# ZXS_I2_kartridz.net
KiCad netlist of a schematic drawn in EAGLE
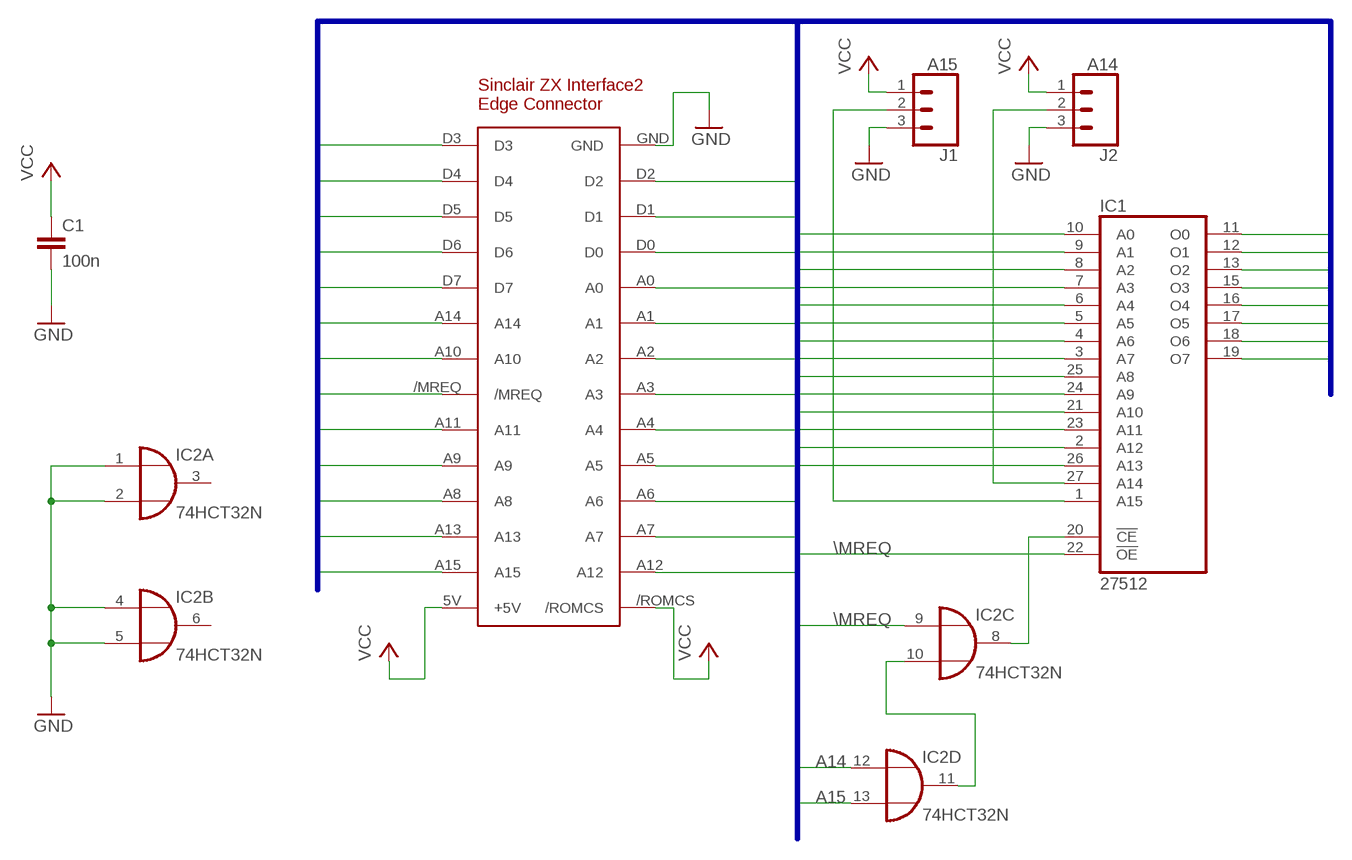
[diagram p0: schematic, sheet 1]

(export (version "E")
  (design (tool "Eeschema 10.0.6"))
  (components
    (comp (ref "C1")
      (value "100n")
      (footprint "eagle-import:C050-024X044")
      (libsource (lib "eagle-import") (part "C-EU050-024X044"))
    )
    (comp (ref "IC1")
      (value "27512")
      (footprint "eagle-import:DIL28")
      (libsource (lib "eagle-import") (part "27512"))
    )
    (comp (ref "IC2")
      (value "74HCT32N")
      (footprint "eagle-import:DIL14")
      (libsource (lib "eagle-import") (part "7432NHCT"))
    )
    (comp (ref "J1")
      (value "A15")
      (footprint "eagle-import:1X03")
      (libsource (lib "eagle-import") (part "CONN_03"))
    )
    (comp (ref "J2")
      (value "A14")
      (footprint "eagle-import:1X03")
      (libsource (lib "eagle-import") (part "CONN_03"))
    )
    (comp (ref "U$1")
      (value "ZX_I2_ROM_EDGE_CONNECTOR")
      (footprint "eagle-import:ZX_I2_ROM_EDGE_CONNECTOR_V2")
      (libsource (lib "eagle-import") (part "ZX_I2_ROM_EDGE_CONNECTOR"))
    )
  )
  (nets
    (net (code "1") (name "/A0") (class "Default")
      (node (ref "IC1") (pin "10") (pinfunction "A0_10") (pintype "input"))
      (node (ref "U$1") (pin "A0") (pinfunction "A0_A0") (pintype "bidirectional"))
    )
    (net (code "2") (name "/A1") (class "Default")
      (node (ref "IC1") (pin "9") (pinfunction "A1_9") (pintype "input"))
      (node (ref "U$1") (pin "A1") (pinfunction "A1_A1") (pintype "bidirectional"))
    )
    (net (code "3") (name "/A2") (class "Default")
      (node (ref "IC1") (pin "8") (pinfunction "A2_8") (pintype "input"))
      (node (ref "U$1") (pin "A2") (pinfunction "A2_A2") (pintype "bidirectional"))
    )
    (net (code "4") (name "/A3") (class "Default")
      (node (ref "IC1") (pin "7") (pinfunction "A3_7") (pintype "input"))
      (node (ref "U$1") (pin "A3") (pinfunction "A3_A3") (pintype "bidirectional"))
    )
    (net (code "5") (name "/A4") (class "Default")
      (node (ref "IC1") (pin "6") (pinfunction "A4_6") (pintype "input"))
      (node (ref "U$1") (pin "A4") (pinfunction "A4_A4") (pintype "bidirectional"))
    )
    (net (code "6") (name "/A5") (class "Default")
      (node (ref "IC1") (pin "5") (pinfunction "A5_5") (pintype "input"))
      (node (ref "U$1") (pin "A5") (pinfunction "A5_A5") (pintype "bidirectional"))
    )
    (net (code "7") (name "/A6") (class "Default")
      (node (ref "IC1") (pin "4") (pinfunction "A6_4") (pintype "input"))
      (node (ref "U$1") (pin "A6") (pinfunction "A6_A6") (pintype "bidirectional"))
    )
    (net (code "8") (name "/A7") (class "Default")
      (node (ref "IC1") (pin "3") (pinfunction "A7_3") (pintype "input"))
      (node (ref "U$1") (pin "A7") (pinfunction "A7_A7") (pintype "bidirectional"))
    )
    (net (code "9") (name "/A8") (class "Default")
      (node (ref "IC1") (pin "25") (pinfunction "A8_25") (pintype "input"))
      (node (ref "U$1") (pin "A8") (pinfunction "A8_A8") (pintype "bidirectional"))
    )
    (net (code "10") (name "/A9") (class "Default")
      (node (ref "IC1") (pin "24") (pinfunction "A9_24") (pintype "input"))
      (node (ref "U$1") (pin "A9") (pinfunction "A9_A9") (pintype "bidirectional"))
    )
    (net (code "11") (name "/A10") (class "Default")
      (node (ref "IC1") (pin "21") (pinfunction "A10_21") (pintype "input"))
      (node (ref "U$1") (pin "A10") (pinfunction "A10_A10") (pintype "bidirectional"))
    )
    (net (code "12") (name "/A11") (class "Default")
      (node (ref "IC1") (pin "23") (pinfunction "A11_23") (pintype "input"))
      (node (ref "U$1") (pin "A11") (pinfunction "A11_A11") (pintype "bidirectional"))
    )
    (net (code "13") (name "/A12") (class "Default")
      (node (ref "IC1") (pin "2") (pinfunction "A12_2") (pintype "input"))
      (node (ref "U$1") (pin "A12") (pinfunction "A12_A12") (pintype "bidirectional"))
    )
    (net (code "14") (name "/A13") (class "Default")
      (node (ref "IC1") (pin "26") (pinfunction "A13_26") (pintype "input"))
      (node (ref "U$1") (pin "A13") (pinfunction "A13_A13") (pintype "bidirectional"))
    )
    (net (code "15") (name "/A14") (class "Default")
      (node (ref "IC2") (pin "12") (pinfunction "I0_12") (pintype "input"))
      (node (ref "U$1") (pin "A14") (pinfunction "A14_A14") (pintype "bidirectional"))
    )
    (net (code "16") (name "/A15") (class "Default")
      (node (ref "IC2") (pin "13") (pinfunction "I1_13") (pintype "input"))
      (node (ref "U$1") (pin "A15") (pinfunction "A15_A15") (pintype "bidirectional"))
    )
    (net (code "17") (name "/D0") (class "Default")
      (node (ref "IC1") (pin "11") (pinfunction "O0_11") (pintype "tri_state"))
      (node (ref "U$1") (pin "D0") (pinfunction "D0_D0") (pintype "bidirectional"))
    )
    (net (code "18") (name "/D1") (class "Default")
      (node (ref "IC1") (pin "12") (pinfunction "O1_12") (pintype "tri_state"))
      (node (ref "U$1") (pin "D1") (pinfunction "D1_D1") (pintype "bidirectional"))
    )
    (net (code "19") (name "/D2") (class "Default")
      (node (ref "IC1") (pin "13") (pinfunction "O2_13") (pintype "tri_state"))
      (node (ref "U$1") (pin "D2") (pinfunction "D2_D2") (pintype "bidirectional"))
    )
    (net (code "20") (name "/D3") (class "Default")
      (node (ref "IC1") (pin "15") (pinfunction "O3_15") (pintype "tri_state"))
      (node (ref "U$1") (pin "D3") (pinfunction "D3_D3") (pintype "bidirectional"))
    )
    (net (code "21") (name "/D4") (class "Default")
      (node (ref "IC1") (pin "16") (pinfunction "O4_16") (pintype "tri_state"))
      (node (ref "U$1") (pin "D4") (pinfunction "D4_D4") (pintype "bidirectional"))
    )
    (net (code "22") (name "/D5") (class "Default")
      (node (ref "IC1") (pin "17") (pinfunction "O5_17") (pintype "tri_state"))
      (node (ref "U$1") (pin "D5") (pinfunction "D5_D5") (pintype "bidirectional"))
    )
    (net (code "23") (name "/D6") (class "Default")
      (node (ref "IC1") (pin "18") (pinfunction "O6_18") (pintype "tri_state"))
      (node (ref "U$1") (pin "D6") (pinfunction "D6_D6") (pintype "bidirectional"))
    )
    (net (code "24") (name "/D7") (class "Default")
      (node (ref "IC1") (pin "19") (pinfunction "O7_19") (pintype "tri_state"))
      (node (ref "U$1") (pin "D7") (pinfunction "D7_D7") (pintype "bidirectional"))
    )
    (net (code "25") (name "/\\MREQ") (class "Default")
      (node (ref "IC1") (pin "22") (pinfunction "~{OE}_22") (pintype "input"))
      (node (ref "IC2") (pin "9") (pinfunction "I0_9") (pintype "input"))
      (node (ref "U$1") (pin "/MREQ") (pinfunction "/MREQ_/MREQ") (pintype "bidirectional"))
    )
    (net (code "26") (name "GND") (class "Default")
      (node (ref "C1") (pin "2") (pinfunction "2_2") (pintype "passive"))
      (node (ref "IC2") (pin "1") (pinfunction "I0_1") (pintype "input"))
      (node (ref "IC2") (pin "2") (pinfunction "I1_2") (pintype "input"))
      (node (ref "IC2") (pin "4") (pinfunction "I0_4") (pintype "input"))
      (node (ref "IC2") (pin "5") (pinfunction "I1_5") (pintype "input"))
      (node (ref "J1") (pin "3") (pinfunction "3_3") (pintype "passive"))
      (node (ref "J2") (pin "3") (pinfunction "3_3") (pintype "passive"))
      (node (ref "U$1") (pin "GND") (pinfunction "GND_GND") (pintype "bidirectional"))
    )
    (net (code "27") (name "Net-(IC1A-A14)") (class "Default")
      (node (ref "IC1") (pin "27") (pinfunction "A14_27") (pintype "input"))
      (node (ref "J2") (pin "2") (pinfunction "2_2") (pintype "passive"))
    )
    (net (code "28") (name "Net-(IC1A-A15)") (class "Default")
      (node (ref "IC1") (pin "1") (pinfunction "A15_1") (pintype "input"))
      (node (ref "J1") (pin "2") (pinfunction "2_2") (pintype "passive"))
    )
    (net (code "29") (name "Net-(IC1A-~{CE})") (class "Default")
      (node (ref "IC1") (pin "20") (pinfunction "~{CE}_20") (pintype "input"))
      (node (ref "IC2") (pin "8") (pinfunction "O_8") (pintype "output"))
    )
    (net (code "30") (name "Net-(IC2C-I1)") (class "Default")
      (node (ref "IC2") (pin "10") (pinfunction "I1_10") (pintype "input"))
      (node (ref "IC2") (pin "11") (pinfunction "O_11") (pintype "output"))
    )
    (net (code "31") (name "VCC") (class "Default")
      (node (ref "C1") (pin "1") (pinfunction "1_1") (pintype "passive"))
      (node (ref "J1") (pin "1") (pinfunction "1_1") (pintype "passive"))
      (node (ref "J2") (pin "1") (pinfunction "1_1") (pintype "passive"))
      (node (ref "U$1") (pin "/ROMCS") (pinfunction "/ROMCS_/ROMCS") (pintype "bidirectional"))
      (node (ref "U$1") (pin "5V") (pinfunction "+5V_5V") (pintype "bidirectional"))
    )
    (net (code "32") (name "unconnected-(IC2A-O-Pad3)") (class "Default")
      (node (ref "IC2") (pin "3") (pinfunction "O_3") (pintype "output"))
    )
    (net (code "33") (name "unconnected-(IC2B-O-Pad6)") (class "Default")
      (node (ref "IC2") (pin "6") (pinfunction "O_6") (pintype "output"))
    )
  )
)
